# CanBus-Breadboard.net
KiCad netlist of a schematic drawn in EAGLE
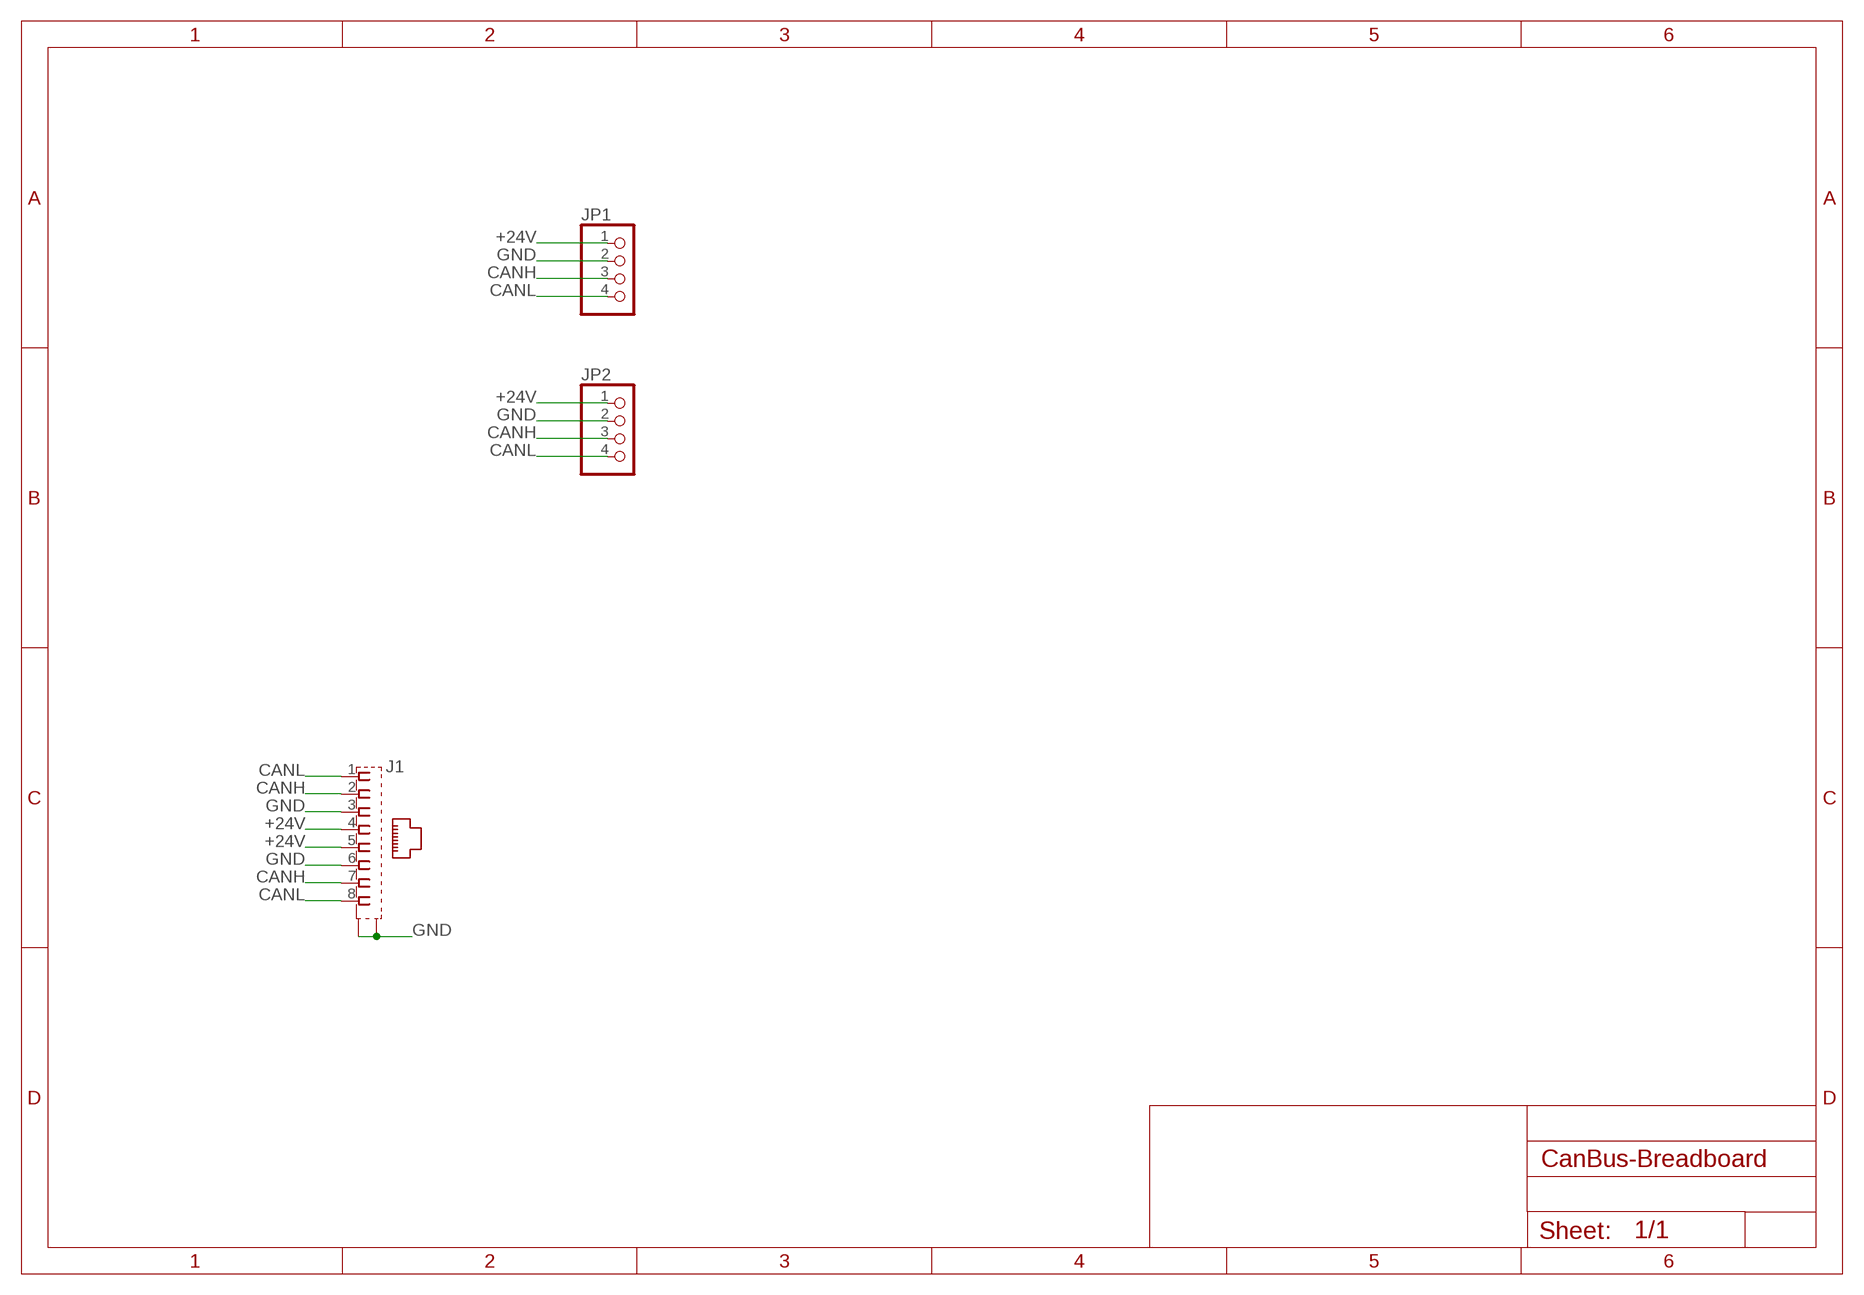
[diagram p0: schematic, sheet 1]

(export (version "E")
  (design (tool "Eeschema 10.0.6"))
  (components
    (comp (ref "J1")
      (value "555141-1")
      (footprint "eagle-import:MEBP_8-8G")
      (libsource (lib "eagle-import") (part "555141-1"))
    )
    (comp (ref "JP1")
      (value "PINHD-1X4")
      (footprint "eagle-import:1X04")
      (libsource (lib "eagle-import") (part "PINHD-1X4"))
    )
    (comp (ref "JP2")
      (value "PINHD-1X4")
      (footprint "eagle-import:1X04")
      (libsource (lib "eagle-import") (part "PINHD-1X4"))
    )
  )
  (nets
    (net (code "1") (name "/+24V") (class "Default")
      (node (ref "J1") (pin "4") (pinfunction "4_4") (pintype "passive"))
      (node (ref "J1") (pin "5") (pinfunction "5_5") (pintype "passive"))
      (node (ref "JP1") (pin "1") (pinfunction "1_1") (pintype "passive"))
      (node (ref "JP2") (pin "1") (pinfunction "1_1") (pintype "passive"))
    )
    (net (code "2") (name "/CANH") (class "Default")
      (node (ref "J1") (pin "2") (pinfunction "2_2") (pintype "passive"))
      (node (ref "J1") (pin "7") (pinfunction "7_7") (pintype "passive"))
      (node (ref "JP1") (pin "3") (pinfunction "3_3") (pintype "passive"))
      (node (ref "JP2") (pin "3") (pinfunction "3_3") (pintype "passive"))
    )
    (net (code "3") (name "/CANL") (class "Default")
      (node (ref "J1") (pin "1") (pinfunction "1_1") (pintype "passive"))
      (node (ref "J1") (pin "8") (pinfunction "8_8") (pintype "passive"))
      (node (ref "JP1") (pin "4") (pinfunction "4_4") (pintype "passive"))
      (node (ref "JP2") (pin "4") (pinfunction "4_4") (pintype "passive"))
    )
    (net (code "4") (name "/GND") (class "Default")
      (node (ref "J1") (pin "3") (pinfunction "3_3") (pintype "passive"))
      (node (ref "J1") (pin "6") (pinfunction "6_6") (pintype "passive"))
      (node (ref "J1") (pin "G1") (pinfunction "S1_G1") (pintype "passive"))
      (node (ref "J1") (pin "G2") (pinfunction "S2_G2") (pintype "passive"))
      (node (ref "JP1") (pin "2") (pinfunction "2_2") (pintype "passive"))
      (node (ref "JP2") (pin "2") (pinfunction "2_2") (pintype "passive"))
    )
  )
)
